# LCD_RGB.net
KiCad netlist of a schematic drawn in Altium Designer
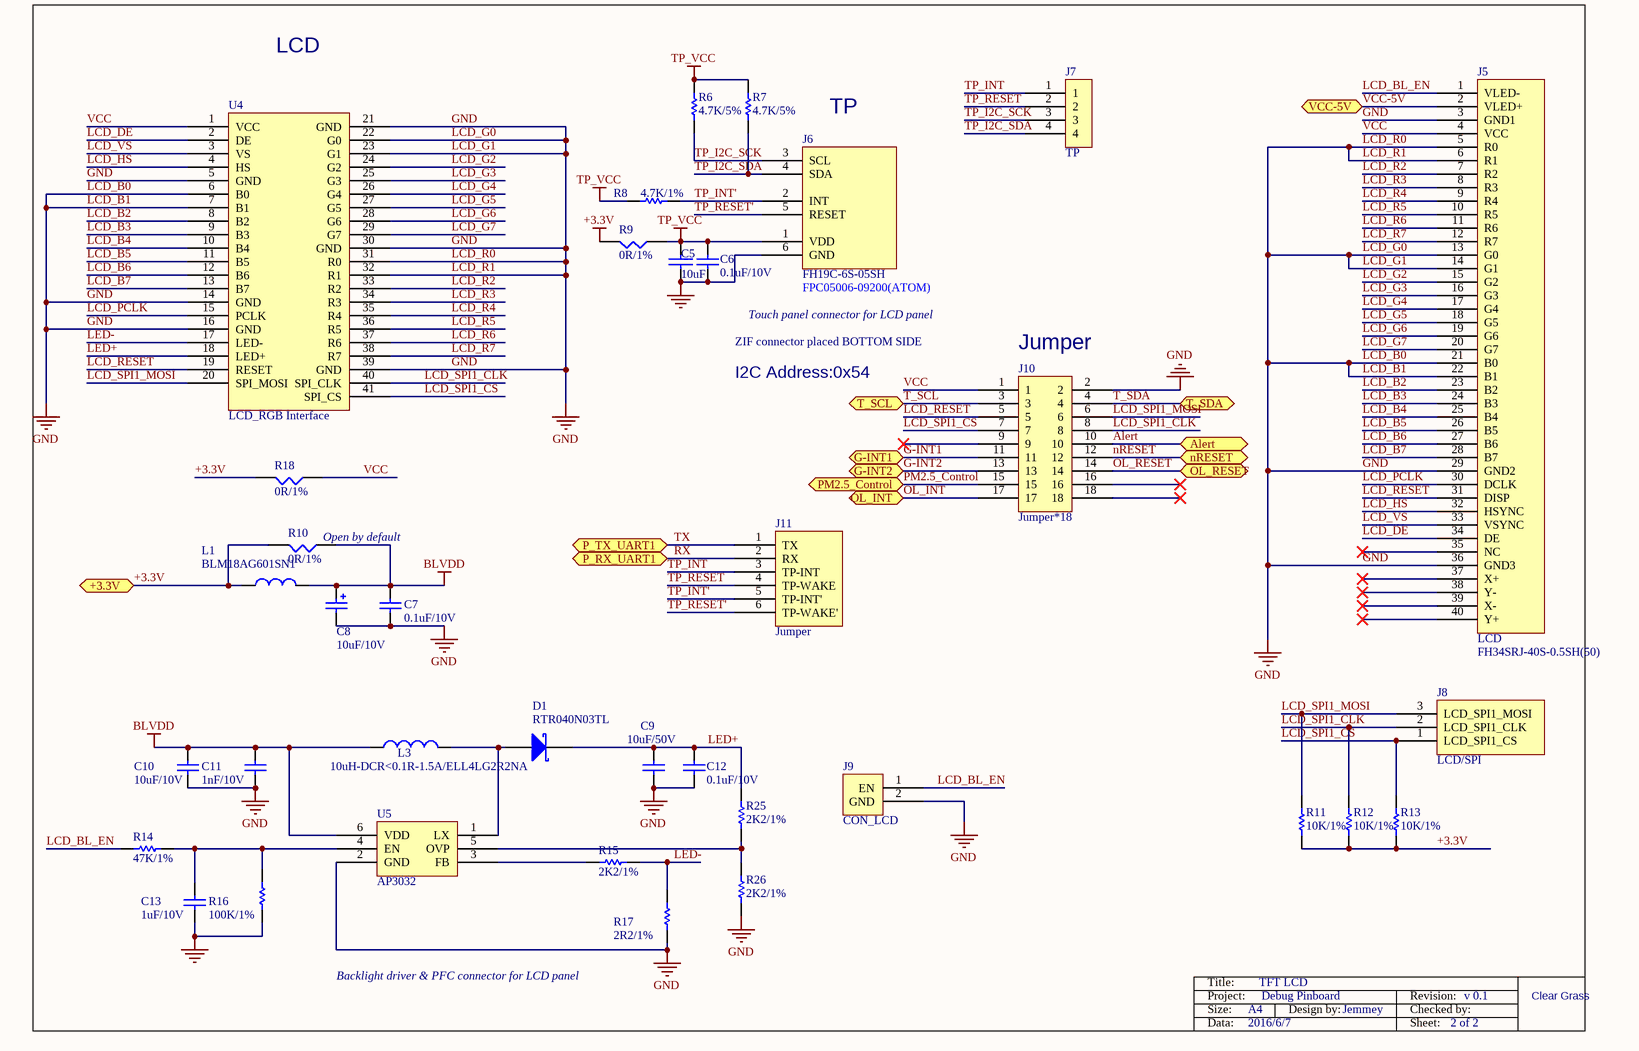
[diagram p0: LCD_RGB.SchDoc]

(export (version "E")
  (design (tool "Eeschema 10.0.6"))
  (components
    (comp (ref "C5")
      (value "10uF")
      (footprint "0603C")
      (description "厂家：Murata，型号：GRM1555C1H120JA01D")
      (libsource (lib "Amber") (part "CAP"))
    )
    (comp (ref "C6")
      (value "0.1uF/10V")
      (footprint "0402C")
      (description "Capacitor")
      (fields (field (name "PUBLISHER") "Altium Limited"))
      (libsource (lib "Miscellaneous Devices") (part "CAP"))
    )
    (comp (ref "C7")
      (value "0.1uF/10V")
      (footprint "0402C")
      (description "Capacitor")
      (fields (field (name "PUBLISHER") "Altium Limited"))
      (libsource (lib "Miscellaneous Devices") (part "Cap"))
    )
    (comp (ref "C8")
      (value "10uF/10V")
      (footprint "0603C")
      (description "Polarized Capacitor (Radial)")
      (fields (field (name "PUBLISHER") "Altium Limited"))
      (libsource (lib "Miscellaneous Devices") (part "Cap Pol1"))
    )
    (comp (ref "C9")
      (value "10uF/50V")
      (footprint "0603C")
      (description "厂家：Murata，型号：")
      (fields (field (name "PUBLISHER") "Altium Limited"))
      (libsource (lib "Miscellaneous Devices") (part "CAP"))
    )
    (comp (ref "C10")
      (value "10uF/10V")
      (footprint "0603C")
      (description "Capacitor")
      (fields (field (name "PUBLISHER") "Altium Limited"))
      (libsource (lib "Miscellaneous Devices") (part "CAP"))
    )
    (comp (ref "C11")
      (value "1nF/10V")
      (footprint "0402C")
      (description "Capacitor")
      (fields (field (name "PUBLISHER") "Altium Limited"))
      (libsource (lib "Miscellaneous Devices") (part "CAP"))
    )
    (comp (ref "C12")
      (value "0.1uF/10V")
      (footprint "0402C")
      (description "厂家：Murata，型号：")
      (fields (field (name "PUBLISHER") "Altium Limited"))
      (libsource (lib "*") (part "CAP"))
    )
    (comp (ref "C13")
      (value "1uF/10V")
      (footprint "0402C")
      (description "Capacitor")
      (fields (field (name "PUBLISHER") "Altium Limited"))
      (libsource (lib "Miscellaneous Devices") (part "CAP"))
    )
    (comp (ref "D1")
      (value "RTR040N03TL")
      (footprint "TUMD2M")
      (description "Schottky Diode")
      (fields (field (name "PUBLISHER") "Altium Limited"))
      (libsource (lib "Miscellaneous Devices") (part "D Schottky"))
    )
    (comp (ref "J5")
      (value "LCD")
      (footprint "FPC_CON40-BACK-IRS")
      (libsource (lib "Debug Pinborad_1") (part "FPC60_1"))
    )
    (comp (ref "J6")
      (value "FH19C-6S-05SH")
      (description "ZIF connector placed bottom side")
      (libsource (lib "MB1166") (part "FH19C-6S-05SH"))
    )
    (comp (ref "J7")
      (value "TP")
      (description "Jumper")
      (libsource (lib "Bran PinBoard") (part "Jumper_uart"))
    )
    (comp (ref "J8")
      (value "LCD/SPI")
      (footprint "2.54*3")
      (description "Jumper")
      (libsource (lib "Debug Pinborad") (part "Jumper"))
    )
    (comp (ref "J9")
      (value "CON_LCD")
      (footprint "2.54*2")
      (libsource (lib "Debug Pinborad") (part "CON_LCD"))
    )
    (comp (ref "J10")
      (value "Jumper*18")
      (footprint "2.54*18")
      (libsource (lib "Bran PinBoard") (part "Jumper*18"))
    )
    (comp (ref "J11")
      (value "Jumper")
      (footprint "2.54*2 *3")
      (libsource (lib "Bran PinBoard_1") (part "Jumper_uart"))
    )
    (comp (ref "L1")
      (value "BLM18AG601SN1")
      (footprint "0603R")
      (description "厂家：MURATA，型号：BLM18AG601SN1")
      (libsource (lib "Amber") (part "CHOKE"))
    )
    (comp (ref "L3")
      (value "10uH-DCR<0.1R-1.5A/ELL4LG2R2NA")
      (footprint "INDM4040X18N")
      (description "Inductor")
      (fields (field (name "PUBLISHER") "Altium Limited"))
      (libsource (lib "Miscellaneous Devices") (part "Inductor"))
    )
    (comp (ref "R6")
      (value "4.7K/5%")
      (footprint "0402R")
      (description "厂家：Yageo，型号：")
      (fields (field (name "PUBLISHER") "Altium Limited"))
      (libsource (lib "*") (part "Res1"))
    )
    (comp (ref "R7")
      (value "4.7K/5%")
      (footprint "0402R")
      (description "厂家：Yageo，型号：")
      (fields (field (name "PUBLISHER") "Altium Limited"))
      (libsource (lib "*") (part "Res1"))
    )
    (comp (ref "R8")
      (value "4.7K/1%")
      (footprint "0402R")
      (description "厂家：Yageo，型号：")
      (fields (field (name "PUBLISHER") "Altium Limited"))
      (libsource (lib "*") (part "Res1"))
    )
    (comp (ref "R9")
      (value "0R/1%")
      (footprint "0603R")
      (description "厂家：Yageo，型号：RC0402FR-070RL")
      (libsource (lib "*") (part "RES1"))
    )
    (comp (ref "R10")
      (value "0R/1%")
      (footprint "0603R")
      (description "厂家：Yageo，型号：RC0402FR-070RL")
      (libsource (lib "*") (part "RES1"))
    )
    (comp (ref "R11")
      (value "10K/1%")
      (footprint "0402R")
      (description "厂家：Yageo，型号：")
      (fields (field (name "PUBLISHER") "Altium Limited"))
      (libsource (lib "*") (part "Res1"))
    )
    (comp (ref "R12")
      (value "10K/1%")
      (footprint "0402R")
      (description "厂家：Yageo，型号：")
      (fields (field (name "PUBLISHER") "Altium Limited"))
      (libsource (lib "*") (part "Res1"))
    )
    (comp (ref "R13")
      (value "10K/1%")
      (footprint "0402R")
      (description "厂家：Yageo，型号：")
      (fields (field (name "PUBLISHER") "Altium Limited"))
      (libsource (lib "*") (part "Res1"))
    )
    (comp (ref "R14")
      (value "47K/1%")
      (footprint "0402R")
      (description "Resistor")
      (fields (field (name "PUBLISHER") "Altium Limited"))
      (libsource (lib "Miscellaneous Devices") (part "Res1"))
    )
    (comp (ref "R15")
      (value "2K2/1%")
      (footprint "0402R")
      (description "Resistor")
      (fields (field (name "PUBLISHER") "Altium Limited"))
      (libsource (lib "Miscellaneous Devices") (part "Res1"))
    )
    (comp (ref "R16")
      (value "100K/1%")
      (footprint "0402R")
      (description "Resistor")
      (fields (field (name "PUBLISHER") "Altium Limited"))
      (libsource (lib "Miscellaneous Devices") (part "Res1"))
    )
    (comp (ref "R17")
      (value "2R2/1%")
      (footprint "0402R")
      (description "Resistor")
      (fields (field (name "PUBLISHER") "Altium Limited"))
      (libsource (lib "Miscellaneous Devices") (part "Res1"))
    )
    (comp (ref "R18")
      (value "0R/1%")
      (footprint "0603R")
      (description "厂家：Yageo，型号：RC0402FR-070RL")
      (libsource (lib "*") (part "RES1"))
    )
    (comp (ref "R25")
      (value "2K2/1%")
      (footprint "0402R")
      (description "Resistor")
      (fields (field (name "PUBLISHER") "Altium Limited"))
      (libsource (lib "Miscellaneous Devices") (part "Res1"))
    )
    (comp (ref "R26")
      (value "2K2/1%")
      (footprint "0402R")
      (description "Resistor")
      (fields (field (name "PUBLISHER") "Altium Limited"))
      (libsource (lib "Miscellaneous Devices") (part "Res1"))
    )
    (comp (ref "U4")
      (value "LCD_RGB Interface")
      (libsource (lib "Debug Pinborad_1") (part "LCD_RGB Interface"))
    )
    (comp (ref "U5")
      (value "AP3032")
      (footprint "SOT23-6-L")
      (libsource (lib "Debug Pinborad") (part "AP3032"))
    )
  )
  (nets
    (net (code "1") (name "+3.3V") (class "Default")
      (node (ref "L1") (pin "1") (pinfunction "1_1") (pintype "passive"))
      (node (ref "R10") (pin "2") (pinfunction "2_2") (pintype "passive"))
      (node (ref "R11") (pin "1") (pinfunction "1_1") (pintype "passive"))
      (node (ref "R12") (pin "1") (pinfunction "1_1") (pintype "passive"))
      (node (ref "R13") (pin "1") (pinfunction "1_1") (pintype "passive"))
      (node (ref "R18") (pin "2") (pinfunction "2_2") (pintype "passive"))
      (node (ref "R9") (pin "2") (pinfunction "2_2") (pintype "passive"))
    )
    (net (code "2") (name "/Alert") (class "Default")
      (node (ref "J10") (pin "10") (pinfunction "10_10") (pintype "passive"))
    )
    (net (code "3") (name "/G-INT1") (class "Default")
      (node (ref "J10") (pin "11") (pinfunction "11_11") (pintype "passive"))
    )
    (net (code "4") (name "/G-INT2") (class "Default")
      (node (ref "J10") (pin "13") (pinfunction "13_13") (pintype "passive"))
    )
    (net (code "5") (name "/LCD_B2") (class "Default")
      (node (ref "J5") (pin "23") (pinfunction "B2_23") (pintype "passive"))
      (node (ref "U4") (pin "8") (pinfunction "B2_8") (pintype "passive"))
    )
    (net (code "6") (name "/LCD_B3") (class "Default")
      (node (ref "J5") (pin "24") (pinfunction "B3_24") (pintype "passive"))
      (node (ref "U4") (pin "9") (pinfunction "B3_9") (pintype "passive"))
    )
    (net (code "7") (name "/LCD_B4") (class "Default")
      (node (ref "J5") (pin "25") (pinfunction "B4_25") (pintype "passive"))
      (node (ref "U4") (pin "10") (pinfunction "B4_10") (pintype "passive"))
    )
    (net (code "8") (name "/LCD_B5") (class "Default")
      (node (ref "J5") (pin "26") (pinfunction "B5_26") (pintype "passive"))
      (node (ref "U4") (pin "11") (pinfunction "B5_11") (pintype "passive"))
    )
    (net (code "9") (name "/LCD_B6") (class "Default")
      (node (ref "J5") (pin "27") (pinfunction "B6_27") (pintype "passive"))
      (node (ref "U4") (pin "12") (pinfunction "B6_12") (pintype "passive"))
    )
    (net (code "10") (name "/LCD_B7") (class "Default")
      (node (ref "J5") (pin "28") (pinfunction "B7_28") (pintype "passive"))
      (node (ref "U4") (pin "13") (pinfunction "B7_13") (pintype "passive"))
    )
    (net (code "11") (name "/LCD_BL_EN") (class "Default")
      (node (ref "J5") (pin "1") (pinfunction "VLED-_1") (pintype "passive"))
      (node (ref "J9") (pin "1") (pinfunction "EN_1") (pintype "passive"))
      (node (ref "R14") (pin "1") (pinfunction "1_1") (pintype "passive"))
    )
    (net (code "12") (name "/LCD_DE") (class "Default")
      (node (ref "J5") (pin "34") (pinfunction "DE_34") (pintype "passive"))
      (node (ref "U4") (pin "2") (pinfunction "DE_2") (pintype "passive"))
    )
    (net (code "13") (name "/LCD_G2") (class "Default")
      (node (ref "J5") (pin "15") (pinfunction "G2_15") (pintype "passive"))
      (node (ref "U4") (pin "24") (pinfunction "G2_24") (pintype "passive"))
    )
    (net (code "14") (name "/LCD_G3") (class "Default")
      (node (ref "J5") (pin "16") (pinfunction "G3_16") (pintype "passive"))
      (node (ref "U4") (pin "25") (pinfunction "G3_25") (pintype "passive"))
    )
    (net (code "15") (name "/LCD_G4") (class "Default")
      (node (ref "J5") (pin "17") (pinfunction "G4_17") (pintype "passive"))
      (node (ref "U4") (pin "26") (pinfunction "G4_26") (pintype "passive"))
    )
    (net (code "16") (name "/LCD_G5") (class "Default")
      (node (ref "J5") (pin "18") (pinfunction "G5_18") (pintype "passive"))
      (node (ref "U4") (pin "27") (pinfunction "G5_27") (pintype "passive"))
    )
    (net (code "17") (name "/LCD_G6") (class "Default")
      (node (ref "J5") (pin "19") (pinfunction "G6_19") (pintype "passive"))
      (node (ref "U4") (pin "28") (pinfunction "G6_28") (pintype "passive"))
    )
    (net (code "18") (name "/LCD_G7") (class "Default")
      (node (ref "J5") (pin "20") (pinfunction "G7_20") (pintype "passive"))
      (node (ref "U4") (pin "29") (pinfunction "G7_29") (pintype "passive"))
    )
    (net (code "19") (name "/LCD_HS") (class "Default")
      (node (ref "J5") (pin "32") (pinfunction "HSYNC_32") (pintype "passive"))
      (node (ref "U4") (pin "4") (pinfunction "HS_4") (pintype "passive"))
    )
    (net (code "20") (name "/LCD_PCLK") (class "Default")
      (node (ref "J5") (pin "30") (pinfunction "DCLK_30") (pintype "passive"))
      (node (ref "U4") (pin "15") (pinfunction "PCLK_15") (pintype "passive"))
    )
    (net (code "21") (name "/LCD_R2") (class "Default")
      (node (ref "J5") (pin "7") (pinfunction "R2_7") (pintype "passive"))
      (node (ref "U4") (pin "33") (pinfunction "R2_33") (pintype "passive"))
    )
    (net (code "22") (name "/LCD_R3") (class "Default")
      (node (ref "J5") (pin "8") (pinfunction "R3_8") (pintype "passive"))
      (node (ref "U4") (pin "34") (pinfunction "R3_34") (pintype "passive"))
    )
    (net (code "23") (name "/LCD_R4") (class "Default")
      (node (ref "J5") (pin "9") (pinfunction "R4_9") (pintype "passive"))
      (node (ref "U4") (pin "35") (pinfunction "R4_35") (pintype "passive"))
    )
    (net (code "24") (name "/LCD_R5") (class "Default")
      (node (ref "J5") (pin "10") (pinfunction "R5_10") (pintype "passive"))
      (node (ref "U4") (pin "36") (pinfunction "R5_36") (pintype "passive"))
    )
    (net (code "25") (name "/LCD_R6") (class "Default")
      (node (ref "J5") (pin "11") (pinfunction "R6_11") (pintype "passive"))
      (node (ref "U4") (pin "37") (pinfunction "R6_37") (pintype "passive"))
    )
    (net (code "26") (name "/LCD_R7") (class "Default")
      (node (ref "J5") (pin "12") (pinfunction "R7_12") (pintype "passive"))
      (node (ref "U4") (pin "38") (pinfunction "R7_38") (pintype "passive"))
    )
    (net (code "27") (name "/LCD_RESET") (class "Default")
      (node (ref "J10") (pin "5") (pinfunction "5_5") (pintype "passive"))
      (node (ref "J5") (pin "31") (pinfunction "DISP_31") (pintype "passive"))
      (node (ref "U4") (pin "19") (pinfunction "RESET_19") (pintype "passive"))
    )
    (net (code "28") (name "/LCD_SPI1_CLK") (class "Default")
      (node (ref "J10") (pin "8") (pinfunction "8_8") (pintype "passive"))
      (node (ref "J8") (pin "2") (pinfunction "LCD_SPI1_CLK_2") (pintype "passive"))
      (node (ref "R12") (pin "2") (pinfunction "2_2") (pintype "passive"))
      (node (ref "U4") (pin "40") (pinfunction "SPI_CLK_40") (pintype "passive"))
    )
    (net (code "29") (name "/LCD_SPI1_CS") (class "Default")
      (node (ref "J10") (pin "7") (pinfunction "7_7") (pintype "passive"))
      (node (ref "J8") (pin "1") (pinfunction "LCD_SPI1_CS_1") (pintype "passive"))
      (node (ref "R13") (pin "2") (pinfunction "2_2") (pintype "passive"))
      (node (ref "U4") (pin "41") (pinfunction "SPI_CS_41") (pintype "passive"))
    )
    (net (code "30") (name "/LCD_SPI1_MOSI") (class "Default")
      (node (ref "J10") (pin "6") (pinfunction "6_6") (pintype "passive"))
      (node (ref "J8") (pin "3") (pinfunction "LCD_SPI1_MOSI_3") (pintype "passive"))
      (node (ref "R11") (pin "2") (pinfunction "2_2") (pintype "passive"))
      (node (ref "U4") (pin "20") (pinfunction "SPI_MOSI_20") (pintype "passive"))
    )
    (net (code "31") (name "/LCD_VS") (class "Default")
      (node (ref "J5") (pin "33") (pinfunction "VSYNC_33") (pintype "passive"))
      (node (ref "U4") (pin "3") (pinfunction "VS_3") (pintype "passive"))
    )
    (net (code "32") (name "/LED+") (class "Default")
      (node (ref "C12") (pin "2") (pinfunction "2_2") (pintype "passive"))
      (node (ref "C9") (pin "1") (pinfunction "1_1") (pintype "passive"))
      (node (ref "D1") (pin "2") (pinfunction "K_2") (pintype "passive"))
      (node (ref "R25") (pin "2") (pinfunction "2_2") (pintype "passive"))
      (node (ref "U4") (pin "18") (pinfunction "LED+_18") (pintype "passive"))
    )
    (net (code "33") (name "/LED-") (class "Default")
      (node (ref "R15") (pin "2") (pinfunction "2_2") (pintype "passive"))
      (node (ref "R17") (pin "1") (pinfunction "1_1") (pintype "passive"))
      (node (ref "U4") (pin "17") (pinfunction "LED-_17") (pintype "passive"))
    )
    (net (code "34") (name "/OL_INT") (class "Default")
      (node (ref "J10") (pin "17") (pinfunction "17_17") (pintype "passive"))
    )
    (net (code "35") (name "/OL_RESET") (class "Default")
      (node (ref "J10") (pin "14") (pinfunction "14_14") (pintype "passive"))
    )
    (net (code "36") (name "/PM2.5_Control") (class "Default")
      (node (ref "J10") (pin "15") (pinfunction "15_15") (pintype "passive"))
    )
    (net (code "37") (name "/RX") (class "Default")
      (node (ref "J11") (pin "2") (pinfunction "RX_2") (pintype "passive"))
    )
    (net (code "38") (name "/TP_I2C_SCK") (class "Default")
      (node (ref "J6") (pin "3") (pinfunction "SCL_3") (pintype "passive"))
      (node (ref "J7") (pin "3") (pinfunction "3_3") (pintype "passive"))
      (node (ref "R6") (pin "1") (pinfunction "1_1") (pintype "passive"))
    )
    (net (code "39") (name "/TP_I2C_SDA") (class "Default")
      (node (ref "J6") (pin "4") (pinfunction "SDA_4") (pintype "passive"))
      (node (ref "J7") (pin "4") (pinfunction "4_4") (pintype "passive"))
      (node (ref "R7") (pin "1") (pinfunction "1_1") (pintype "passive"))
    )
    (net (code "40") (name "/TP_INT") (class "Default")
      (node (ref "J11") (pin "3") (pinfunction "TP-INT_3") (pintype "passive"))
      (node (ref "J7") (pin "1") (pinfunction "1_1") (pintype "passive"))
    )
    (net (code "41") (name "/TP_INT'") (class "Default")
      (node (ref "J11") (pin "5") (pinfunction "TP-INT'_5") (pintype "passive"))
      (node (ref "J6") (pin "2") (pinfunction "INT_2") (pintype "passive"))
      (node (ref "R8") (pin "2") (pinfunction "2_2") (pintype "passive"))
    )
    (net (code "42") (name "/TP_RESET") (class "Default")
      (node (ref "J11") (pin "4") (pinfunction "TP-WAKE_4") (pintype "passive"))
      (node (ref "J7") (pin "2") (pinfunction "2_2") (pintype "passive"))
    )
    (net (code "43") (name "/TP_RESET'") (class "Default")
      (node (ref "J11") (pin "6") (pinfunction "TP-WAKE'_6") (pintype "passive"))
      (node (ref "J6") (pin "5") (pinfunction "RESET_5") (pintype "passive"))
    )
    (net (code "44") (name "/TX") (class "Default")
      (node (ref "J11") (pin "1") (pinfunction "TX_1") (pintype "passive"))
    )
    (net (code "45") (name "/T_SCL") (class "Default")
      (node (ref "J10") (pin "3") (pinfunction "3_3") (pintype "passive"))
    )
    (net (code "46") (name "/T_SDA") (class "Default")
      (node (ref "J10") (pin "4") (pinfunction "4_4") (pintype "passive"))
    )
    (net (code "47") (name "/VCC") (class "Default")
      (node (ref "J10") (pin "1") (pinfunction "1_1") (pintype "passive"))
      (node (ref "J5") (pin "4") (pinfunction "VCC_4") (pintype "passive"))
      (node (ref "R18") (pin "1") (pinfunction "1_1") (pintype "passive"))
      (node (ref "U4") (pin "1") (pinfunction "VCC_1") (pintype "passive"))
    )
    (net (code "48") (name "/VCC-5V") (class "Default")
      (node (ref "J5") (pin "2") (pinfunction "VLED+_2") (pintype "passive"))
    )
    (net (code "49") (name "/nRESET") (class "Default")
      (node (ref "J10") (pin "12") (pinfunction "12_12") (pintype "passive"))
    )
    (net (code "50") (name "BLVDD") (class "Default")
      (node (ref "C10") (pin "2") (pinfunction "2_2") (pintype "passive"))
      (node (ref "C11") (pin "2") (pinfunction "2_2") (pintype "passive"))
      (node (ref "C7") (pin "1") (pinfunction "1_1") (pintype "passive"))
      (node (ref "C8") (pin "1") (pinfunction "1_1") (pintype "passive"))
      (node (ref "L1") (pin "2") (pinfunction "2_2") (pintype "passive"))
      (node (ref "L3") (pin "1") (pinfunction "1_1") (pintype "passive"))
      (node (ref "R10") (pin "1") (pinfunction "1_1") (pintype "passive"))
      (node (ref "U5") (pin "6") (pinfunction "VDD_6") (pintype "passive"))
    )
    (net (code "51") (name "GND") (class "Default")
      (node (ref "C10") (pin "1") (pinfunction "1_1") (pintype "passive"))
      (node (ref "C11") (pin "1") (pinfunction "1_1") (pintype "passive"))
      (node (ref "C12") (pin "1") (pinfunction "1_1") (pintype "passive"))
      (node (ref "C13") (pin "1") (pinfunction "1_1") (pintype "passive"))
      (node (ref "C5") (pin "1") (pinfunction "1_1") (pintype "passive"))
      (node (ref "C6") (pin "1") (pinfunction "1_1") (pintype "passive"))
      (node (ref "C7") (pin "2") (pinfunction "2_2") (pintype "passive"))
      (node (ref "C8") (pin "2") (pinfunction "2_2") (pintype "passive"))
      (node (ref "C9") (pin "2") (pinfunction "2_2") (pintype "passive"))
      (node (ref "J10") (pin "2") (pinfunction "2_2") (pintype "passive"))
      (node (ref "J5") (pin "13") (pinfunction "G0_13") (pintype "passive"))
      (node (ref "J5") (pin "14") (pinfunction "G1_14") (pintype "passive"))
      (node (ref "J5") (pin "21") (pinfunction "B0_21") (pintype "passive"))
      (node (ref "J5") (pin "22") (pinfunction "B1_22") (pintype "passive"))
      (node (ref "J5") (pin "29") (pinfunction "GND2_29") (pintype "passive"))
      (node (ref "J5") (pin "3") (pinfunction "GND1_3") (pintype "passive"))
      (node (ref "J5") (pin "36") (pinfunction "GND3_36") (pintype "passive"))
      (node (ref "J5") (pin "5") (pinfunction "R0_5") (pintype "passive"))
      (node (ref "J5") (pin "6") (pinfunction "R1_6") (pintype "passive"))
      (node (ref "J6") (pin "6") (pinfunction "GND_6") (pintype "passive"))
      (node (ref "J9") (pin "2") (pinfunction "GND_2") (pintype "passive"))
      (node (ref "R16") (pin "2") (pinfunction "2_2") (pintype "passive"))
      (node (ref "R17") (pin "2") (pinfunction "2_2") (pintype "passive"))
      (node (ref "R26") (pin "1") (pinfunction "1_1") (pintype "passive"))
      (node (ref "U4") (pin "14") (pinfunction "GND_14") (pintype "passive"))
      (node (ref "U4") (pin "16") (pinfunction "GND_16") (pintype "passive"))
      (node (ref "U4") (pin "21") (pinfunction "GND_21") (pintype "passive"))
      (node (ref "U4") (pin "22") (pinfunction "G0_22") (pintype "passive"))
      (node (ref "U4") (pin "23") (pinfunction "G1_23") (pintype "passive"))
      (node (ref "U4") (pin "30") (pinfunction "GND_30") (pintype "passive"))
      (node (ref "U4") (pin "31") (pinfunction "R0_31") (pintype "passive"))
      (node (ref "U4") (pin "32") (pinfunction "R1_32") (pintype "passive"))
      (node (ref "U4") (pin "39") (pinfunction "GND_39") (pintype "passive"))
      (node (ref "U4") (pin "5") (pinfunction "GND_5") (pintype "passive"))
      (node (ref "U4") (pin "6") (pinfunction "B0_6") (pintype "passive"))
      (node (ref "U4") (pin "7") (pinfunction "B1_7") (pintype "passive"))
      (node (ref "U5") (pin "2") (pinfunction "GND_2") (pintype "passive"))
    )
    (net (code "52") (name "Net-(D1-A)") (class "Default")
      (node (ref "D1") (pin "1") (pinfunction "A_1") (pintype "passive"))
      (node (ref "L3") (pin "2") (pinfunction "2_2") (pintype "passive"))
      (node (ref "U5") (pin "1") (pinfunction "LX_1") (pintype "passive"))
    )
    (net (code "53") (name "Net-(U5-EN)") (class "Default")
      (node (ref "C13") (pin "2") (pinfunction "2_2") (pintype "passive"))
      (node (ref "R14") (pin "2") (pinfunction "2_2") (pintype "passive"))
      (node (ref "R16") (pin "1") (pinfunction "1_1") (pintype "passive"))
      (node (ref "U5") (pin "4") (pinfunction "EN_4") (pintype "passive"))
    )
    (net (code "54") (name "Net-(U5-FB)") (class "Default")
      (node (ref "R15") (pin "1") (pinfunction "1_1") (pintype "passive"))
      (node (ref "U5") (pin "3") (pinfunction "FB_3") (pintype "passive"))
    )
    (net (code "55") (name "Net-(U5-OVP)") (class "Default")
      (node (ref "R25") (pin "1") (pinfunction "1_1") (pintype "passive"))
      (node (ref "R26") (pin "2") (pinfunction "2_2") (pintype "passive"))
      (node (ref "U5") (pin "5") (pinfunction "OVP_5") (pintype "passive"))
    )
    (net (code "56") (name "TP_VCC") (class "Default")
      (node (ref "C5") (pin "2") (pinfunction "2_2") (pintype "passive"))
      (node (ref "C6") (pin "2") (pinfunction "2_2") (pintype "passive"))
      (node (ref "J6") (pin "1") (pinfunction "VDD_1") (pintype "passive"))
      (node (ref "R6") (pin "2") (pinfunction "2_2") (pintype "passive"))
      (node (ref "R7") (pin "2") (pinfunction "2_2") (pintype "passive"))
      (node (ref "R8") (pin "1") (pinfunction "1_1") (pintype "passive"))
      (node (ref "R9") (pin "1") (pinfunction "1_1") (pintype "passive"))
    )
    (net (code "57") (name "unconnected-(J5-NC-Pad35)") (class "Default")
      (node (ref "J5") (pin "35") (pinfunction "NC_35") (pintype "passive+no_connect"))
    )
    (net (code "58") (name "unconnected-(J5-X+-Pad37)") (class "Default")
      (node (ref "J5") (pin "37") (pinfunction "X+_37") (pintype "passive+no_connect"))
    )
    (net (code "59") (name "unconnected-(J5-X--Pad39)") (class "Default")
      (node (ref "J5") (pin "39") (pinfunction "X-_39") (pintype "passive+no_connect"))
    )
    (net (code "60") (name "unconnected-(J5-Y+-Pad40)") (class "Default")
      (node (ref "J5") (pin "40") (pinfunction "Y+_40") (pintype "passive+no_connect"))
    )
    (net (code "61") (name "unconnected-(J5-Y--Pad38)") (class "Default")
      (node (ref "J5") (pin "38") (pinfunction "Y-_38") (pintype "passive+no_connect"))
    )
    (net (code "62") (name "unconnected-(J10-Pad9)") (class "Default")
      (node (ref "J10") (pin "9") (pinfunction "9_9") (pintype "passive+no_connect"))
    )
    (net (code "63") (name "unconnected-(J10-Pad16)") (class "Default")
      (node (ref "J10") (pin "16") (pinfunction "16_16") (pintype "passive+no_connect"))
    )
    (net (code "64") (name "unconnected-(J10-Pad18)") (class "Default")
      (node (ref "J10") (pin "18") (pinfunction "18_18") (pintype "passive+no_connect"))
    )
  )
)
